# 03_constant_temp.net
KiCad netlist of a schematic drawn in Altium Designer
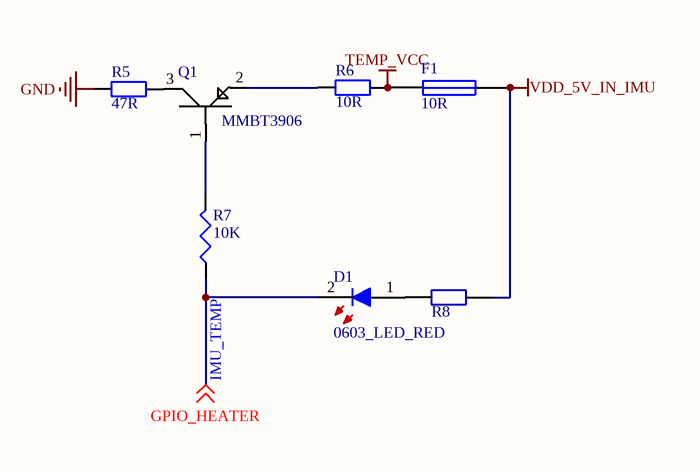
[diagram p0: 03_constant_temp.SchDoc]

(export (version "E")
  (design (tool "Eeschema 10.0.6"))
  (components
    (comp (ref "D1")
      (value "0603_LED_RED")
      (footprint "0603-LED-RED")
      (libsource (lib "CUAV") (part "0603_LED_RED"))
    )
    (comp (ref "F1")
      (value "10R")
      (footprint "0805L")
      (description "Fuse")
      (fields (field (name "PUBLISHER") "Altium Limited"))
      (libsource (lib "Miscellaneous Devices") (part "Fuse 1"))
    )
    (comp (ref "Q1") (value "MMBT3906") (footprint "SOT-23") (libsource (lib "hack") (part "MMBT3906")))
    (comp (ref "R5")
      (value "47R")
      (description "Resistor")
      (fields (field (name "PUBLISHER") "Altium Limited"))
      (libsource (lib "Miscellaneous Devices") (part "Res2"))
    )
    (comp (ref "R6")
      (value "10R")
      (description "Resistor")
      (fields (field (name "PUBLISHER") "Altium Limited"))
      (libsource (lib "Miscellaneous Devices") (part "Res2"))
    )
    (comp (ref "R7")
      (value "10K")
      (footprint "0402r")
      (description "RES TF 4.99K OHM 1% 1/16W 0402")
      (fields
        (field (name "MANUFACTURER") "Stackpole Electronics Inc")
        (field (name "MANUFACTURER PART NUMBER") "RMCF0402FT4K99")
      )
      (libsource (lib "Integrated_Library_RF_FEB_2012") (part "RMCF0402FT4K99"))
    )
    (comp (ref "R8")
      (value "2K")
      (footprint "0402R")
      (description "0402R100R 1%")
      (libsource (lib "CUAV") (part "0402R100R"))
    )
  )
  (nets
    (net (code "1") (name "GND") (class "Default")
      (node (ref "R5") (pin "1") (pinfunction "1_1") (pintype "passive"))
    )
    (net (code "2") (name "GPIO_HEATER") (class "Default")
      (node (ref "D1") (pin "2") (pintype "passive"))
      (node (ref "R7") (pin "1") (pinfunction "1_1") (pintype "passive"))
    )
    (net (code "3") (name "Net-(D1-Pad1)") (class "Default")
      (node (ref "D1") (pin "1") (pintype "passive"))
      (node (ref "R8") (pin "2") (pintype "passive"))
    )
    (net (code "4") (name "Net-(Q1-base)") (class "Default")
      (node (ref "Q1") (pin "1") (pinfunction "base_1") (pintype "passive"))
      (node (ref "R7") (pin "2") (pinfunction "2_2") (pintype "passive"))
    )
    (net (code "5") (name "Net-(Q1-collector)") (class "Default")
      (node (ref "Q1") (pin "3") (pinfunction "collector_3") (pintype "passive"))
      (node (ref "R5") (pin "2") (pinfunction "2_2") (pintype "passive"))
    )
    (net (code "6") (name "Net-(Q1-emitter)") (class "Default")
      (node (ref "Q1") (pin "2") (pinfunction "emitter_2") (pintype "passive"))
      (node (ref "R6") (pin "1") (pinfunction "1_1") (pintype "passive"))
    )
    (net (code "7") (name "TEMP_VCC") (class "Default")
      (node (ref "F1") (pin "1") (pinfunction "1_1") (pintype "passive"))
      (node (ref "R6") (pin "2") (pinfunction "2_2") (pintype "passive"))
    )
    (net (code "8") (name "VDD_5V_IN_IMU") (class "Default")
      (node (ref "F1") (pin "2") (pinfunction "2_2") (pintype "passive"))
      (node (ref "R8") (pin "1") (pintype "passive"))
    )
  )
)
